# Dice-v1.net
KiCad netlist of a schematic drawn in EAGLE
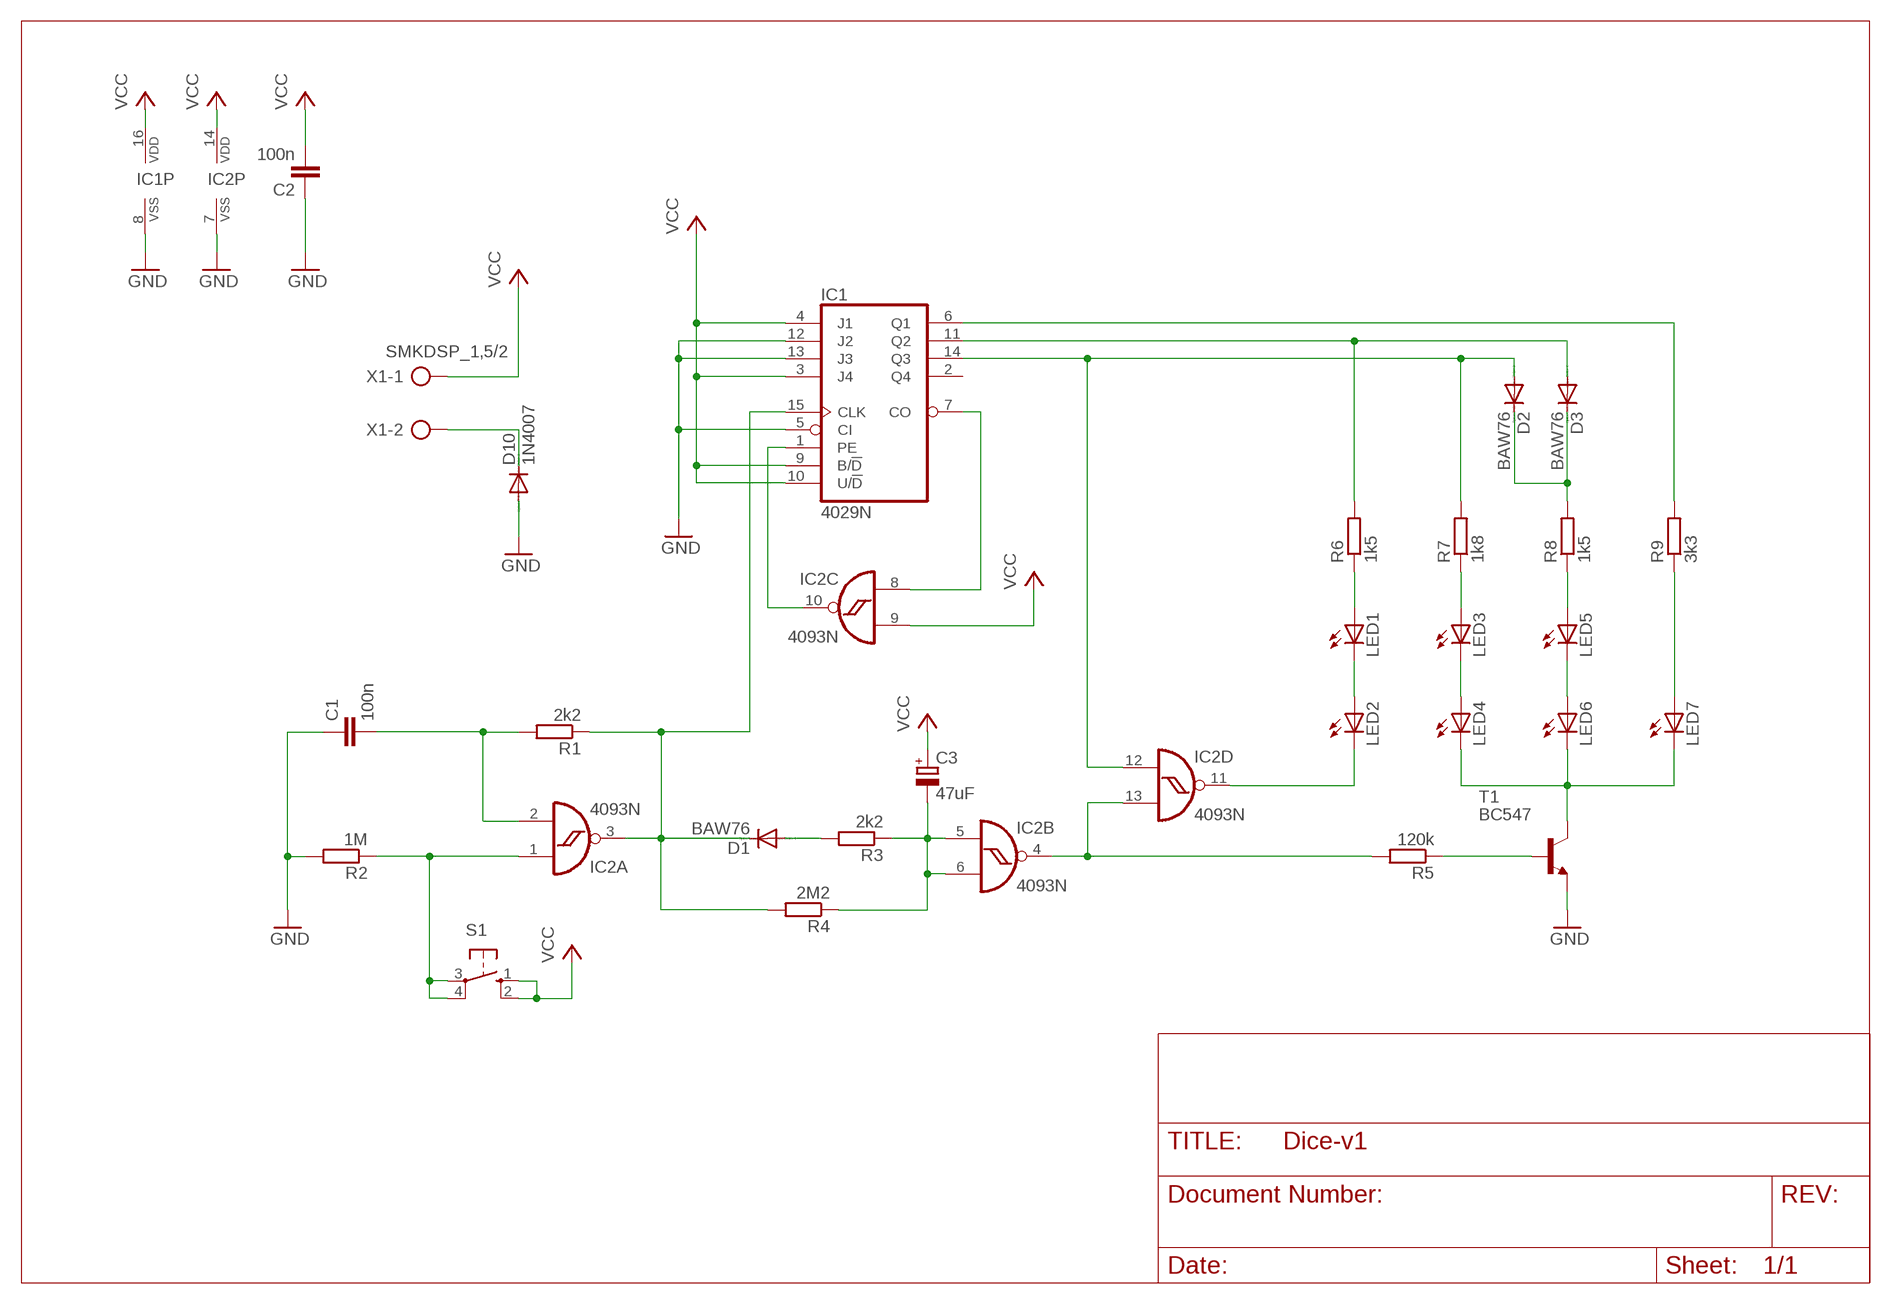
[diagram p0: schematic, sheet 1]

(export (version "E")
  (design (tool "Eeschema 10.0.6"))
  (components
    (comp (ref "C1")
      (value "100n")
      (footprint "eagle-import:C050-025X075")
      (libsource (lib "eagle-import") (part "C-EU050-025X075"))
    )
    (comp (ref "C2")
      (value "100n")
      (footprint "eagle-import:C050-025X075")
      (libsource (lib "eagle-import") (part "C-EU050-025X075"))
    )
    (comp (ref "C3")
      (value "47uF")
      (footprint "eagle-import:E2-5")
      (libsource (lib "eagle-import") (part "CPOL-EUE2-5"))
    )
    (comp (ref "D1")
      (value "BAW76")
      (footprint "eagle-import:DO35-10")
      (libsource (lib "eagle-import") (part "BAW75"))
    )
    (comp (ref "D2")
      (value "BAW76")
      (footprint "eagle-import:DO35-10")
      (libsource (lib "eagle-import") (part "BAW75"))
    )
    (comp (ref "D3")
      (value "BAW76")
      (footprint "eagle-import:DO35-10")
      (libsource (lib "eagle-import") (part "BAW75"))
    )
    (comp (ref "D10")
      (value "1N4007")
      (footprint "eagle-import:DO41-10")
      (libsource (lib "eagle-import") (part "1N4004"))
    )
    (comp (ref "IC1")
      (value "4029N")
      (footprint "eagle-import:DIL16")
      (libsource (lib "eagle-import") (part "4029N"))
    )
    (comp (ref "IC2")
      (value "4093N")
      (footprint "eagle-import:DIL14")
      (libsource (lib "eagle-import") (part "4093N"))
    )
    (comp (ref "LED1")
      (value "LED5MM")
      (footprint "eagle-import:LED5MM")
      (libsource (lib "eagle-import") (part "LED5MM"))
    )
    (comp (ref "LED2")
      (value "LED5MM")
      (footprint "eagle-import:LED5MM")
      (libsource (lib "eagle-import") (part "LED5MM"))
    )
    (comp (ref "LED3")
      (value "LED5MM")
      (footprint "eagle-import:LED5MM")
      (libsource (lib "eagle-import") (part "LED5MM"))
    )
    (comp (ref "LED4")
      (value "LED5MM")
      (footprint "eagle-import:LED5MM")
      (libsource (lib "eagle-import") (part "LED5MM"))
    )
    (comp (ref "LED5")
      (value "LED5MM")
      (footprint "eagle-import:LED5MM")
      (libsource (lib "eagle-import") (part "LED5MM"))
    )
    (comp (ref "LED6")
      (value "LED5MM")
      (footprint "eagle-import:LED5MM")
      (libsource (lib "eagle-import") (part "LED5MM"))
    )
    (comp (ref "LED7")
      (value "LED5MM")
      (footprint "eagle-import:LED5MM")
      (libsource (lib "eagle-import") (part "LED5MM"))
    )
    (comp (ref "R1")
      (value "2k2")
      (footprint "eagle-import:0207_10")
      (libsource (lib "eagle-import") (part "R-EU_0207/10"))
    )
    (comp (ref "R2")
      (value "1M")
      (footprint "eagle-import:0207_10")
      (libsource (lib "eagle-import") (part "R-EU_0207/10"))
    )
    (comp (ref "R3")
      (value "2k2")
      (footprint "eagle-import:0207_10")
      (libsource (lib "eagle-import") (part "R-EU_0207/10"))
    )
    (comp (ref "R4")
      (value "2M2")
      (footprint "eagle-import:0207_10")
      (libsource (lib "eagle-import") (part "R-EU_0207/10"))
    )
    (comp (ref "R5")
      (value "120k")
      (footprint "eagle-import:0207_10")
      (libsource (lib "eagle-import") (part "R-EU_0207/10"))
    )
    (comp (ref "R6")
      (value "1k5")
      (footprint "eagle-import:0207_10")
      (libsource (lib "eagle-import") (part "R-EU_0207/10"))
    )
    (comp (ref "R7")
      (value "1k8")
      (footprint "eagle-import:0207_10")
      (libsource (lib "eagle-import") (part "R-EU_0207/10"))
    )
    (comp (ref "R8")
      (value "1k5")
      (footprint "eagle-import:0207_10")
      (libsource (lib "eagle-import") (part "R-EU_0207/10"))
    )
    (comp (ref "R9")
      (value "3k3")
      (footprint "eagle-import:0207_10")
      (libsource (lib "eagle-import") (part "R-EU_0207/10"))
    )
    (comp (ref "S1")
      (value "10-XX")
      (footprint "eagle-import:B3F-10XX")
      (fields (field (name "MPN") "B3F-1000"))
      (libsource (lib "eagle-import") (part "10-XX"))
    )
    (comp (ref "T1")
      (value "BC547")
      (footprint "eagle-import:TO92")
      (libsource (lib "eagle-import") (part "BC547"))
    )
    (comp (ref "X1")
      (value "SMKDSP_1,5/2")
      (footprint "eagle-import:SMKDSP_1,5_2")
      (fields (field (name "MF") "FARNELL") (field (name "MPN") "1733570"))
      (libsource (lib "eagle-import") (part "SMKDSP_1,5/2"))
    )
  )
  (nets
    (net (code "1") (name "GND") (class "Default")
      (node (ref "C1") (pin "1") (pinfunction "1_1") (pintype "passive"))
      (node (ref "C2") (pin "1") (pinfunction "1_1") (pintype "passive"))
      (node (ref "D10") (pin "A") (pinfunction "A_A") (pintype "passive"))
      (node (ref "IC1") (pin "12") (pinfunction "J2_12") (pintype "input"))
      (node (ref "IC1") (pin "13") (pinfunction "J3_13") (pintype "input"))
      (node (ref "IC1") (pin "5") (pinfunction "CI_5") (pintype "input"))
      (node (ref "IC1") (pin "8") (pinfunction "VSS_8") (pintype "power_in"))
      (node (ref "IC2") (pin "7") (pinfunction "VSS_7") (pintype "power_in"))
      (node (ref "R2") (pin "2") (pinfunction "2_2") (pintype "passive"))
      (node (ref "T1") (pin "1") (pinfunction "E_1") (pintype "passive"))
    )
    (net (code "2") (name "Net-(D1-PadA)") (class "Default")
      (node (ref "D1") (pin "A") (pinfunction "A_A") (pintype "passive"))
      (node (ref "R3") (pin "2") (pinfunction "2_2") (pintype "passive"))
    )
    (net (code "3") (name "Net-(D2-PadC)") (class "Default")
      (node (ref "D2") (pin "C") (pinfunction "C_C") (pintype "passive"))
      (node (ref "D3") (pin "C") (pinfunction "C_C") (pintype "passive"))
      (node (ref "R8") (pin "2") (pinfunction "2_2") (pintype "passive"))
    )
    (net (code "4") (name "Net-(IC1A-CLK)") (class "Default")
      (node (ref "D1") (pin "C") (pinfunction "C_C") (pintype "passive"))
      (node (ref "IC1") (pin "15") (pinfunction "CLK_15") (pintype "input"))
      (node (ref "IC2") (pin "3") (pinfunction "O_3") (pintype "output"))
      (node (ref "R1") (pin "1") (pinfunction "1_1") (pintype "passive"))
      (node (ref "R4") (pin "2") (pinfunction "2_2") (pintype "passive"))
    )
    (net (code "5") (name "Net-(IC1A-CO)") (class "Default")
      (node (ref "IC1") (pin "7") (pinfunction "CO_7") (pintype "output"))
      (node (ref "IC2") (pin "8") (pinfunction "I0_8") (pintype "input"))
    )
    (net (code "6") (name "Net-(IC1A-PE)") (class "Default")
      (node (ref "IC1") (pin "1") (pinfunction "PE_1") (pintype "input"))
      (node (ref "IC2") (pin "10") (pinfunction "O_10") (pintype "output"))
    )
    (net (code "7") (name "Net-(IC1A-Q1)") (class "Default")
      (node (ref "IC1") (pin "6") (pinfunction "Q1_6") (pintype "output"))
      (node (ref "R9") (pin "2") (pinfunction "2_2") (pintype "passive"))
    )
    (net (code "8") (name "Net-(IC1A-Q2)") (class "Default")
      (node (ref "D3") (pin "A") (pinfunction "A_A") (pintype "passive"))
      (node (ref "IC1") (pin "11") (pinfunction "Q2_11") (pintype "output"))
      (node (ref "R6") (pin "2") (pinfunction "2_2") (pintype "passive"))
    )
    (net (code "9") (name "Net-(IC1A-Q3)") (class "Default")
      (node (ref "D2") (pin "A") (pinfunction "A_A") (pintype "passive"))
      (node (ref "IC1") (pin "14") (pinfunction "Q3_14") (pintype "output"))
      (node (ref "IC2") (pin "12") (pinfunction "I0_12") (pintype "input"))
      (node (ref "R7") (pin "2") (pinfunction "2_2") (pintype "passive"))
    )
    (net (code "10") (name "Net-(IC2A-I0)") (class "Default")
      (node (ref "IC2") (pin "1") (pinfunction "I0_1") (pintype "input"))
      (node (ref "R2") (pin "1") (pinfunction "1_1") (pintype "passive"))
      (node (ref "S1") (pin "3") (pinfunction "P_3") (pintype "passive"))
      (node (ref "S1") (pin "4") (pinfunction "P1_4") (pintype "passive"))
    )
    (net (code "11") (name "Net-(IC2A-I1)") (class "Default")
      (node (ref "C1") (pin "2") (pinfunction "2_2") (pintype "passive"))
      (node (ref "IC2") (pin "2") (pinfunction "I1_2") (pintype "input"))
      (node (ref "R1") (pin "2") (pinfunction "2_2") (pintype "passive"))
    )
    (net (code "12") (name "Net-(IC2B-I0)") (class "Default")
      (node (ref "C3") (pin "-") (pinfunction "-_-") (pintype "passive"))
      (node (ref "IC2") (pin "5") (pinfunction "I0_5") (pintype "input"))
      (node (ref "IC2") (pin "6") (pinfunction "I1_6") (pintype "input"))
      (node (ref "R3") (pin "1") (pinfunction "1_1") (pintype "passive"))
      (node (ref "R4") (pin "1") (pinfunction "1_1") (pintype "passive"))
    )
    (net (code "13") (name "Net-(IC2B-O)") (class "Default")
      (node (ref "IC2") (pin "13") (pinfunction "I1_13") (pintype "input"))
      (node (ref "IC2") (pin "4") (pinfunction "O_4") (pintype "output"))
      (node (ref "R5") (pin "2") (pinfunction "2_2") (pintype "passive"))
    )
    (net (code "14") (name "Net-(IC2D-O)") (class "Default")
      (node (ref "IC2") (pin "11") (pinfunction "O_11") (pintype "output"))
      (node (ref "LED2") (pin "K") (pinfunction "C_K") (pintype "passive"))
    )
    (net (code "15") (name "Net-(LED1-C)") (class "Default")
      (node (ref "LED1") (pin "K") (pinfunction "C_K") (pintype "passive"))
      (node (ref "LED2") (pin "A") (pinfunction "A_A") (pintype "passive"))
    )
    (net (code "16") (name "Net-(LED1-PadA)") (class "Default")
      (node (ref "LED1") (pin "A") (pinfunction "A_A") (pintype "passive"))
      (node (ref "R6") (pin "1") (pinfunction "1_1") (pintype "passive"))
    )
    (net (code "17") (name "Net-(LED3-C)") (class "Default")
      (node (ref "LED3") (pin "K") (pinfunction "C_K") (pintype "passive"))
      (node (ref "LED4") (pin "A") (pinfunction "A_A") (pintype "passive"))
    )
    (net (code "18") (name "Net-(LED3-PadA)") (class "Default")
      (node (ref "LED3") (pin "A") (pinfunction "A_A") (pintype "passive"))
      (node (ref "R7") (pin "1") (pinfunction "1_1") (pintype "passive"))
    )
    (net (code "19") (name "Net-(LED4-C)") (class "Default")
      (node (ref "LED4") (pin "K") (pinfunction "C_K") (pintype "passive"))
      (node (ref "LED6") (pin "K") (pinfunction "C_K") (pintype "passive"))
      (node (ref "LED7") (pin "K") (pinfunction "C_K") (pintype "passive"))
      (node (ref "T1") (pin "3") (pinfunction "C_3") (pintype "passive"))
    )
    (net (code "20") (name "Net-(LED5-C)") (class "Default")
      (node (ref "LED5") (pin "K") (pinfunction "C_K") (pintype "passive"))
      (node (ref "LED6") (pin "A") (pinfunction "A_A") (pintype "passive"))
    )
    (net (code "21") (name "Net-(LED5-PadA)") (class "Default")
      (node (ref "LED5") (pin "A") (pinfunction "A_A") (pintype "passive"))
      (node (ref "R8") (pin "1") (pinfunction "1_1") (pintype "passive"))
    )
    (net (code "22") (name "Net-(LED7-PadA)") (class "Default")
      (node (ref "LED7") (pin "A") (pinfunction "A_A") (pintype "passive"))
      (node (ref "R9") (pin "1") (pinfunction "1_1") (pintype "passive"))
    )
    (net (code "23") (name "Net-(T1-B)") (class "Default")
      (node (ref "R5") (pin "1") (pinfunction "1_1") (pintype "passive"))
      (node (ref "T1") (pin "2") (pinfunction "B_2") (pintype "passive"))
    )
    (net (code "24") (name "Net-(X1B-KL)") (class "Default")
      (node (ref "D10") (pin "C") (pinfunction "C_C") (pintype "passive"))
      (node (ref "X1") (pin "2") (pinfunction "KL_2") (pintype "passive"))
    )
    (net (code "25") (name "VCC") (class "Default")
      (node (ref "C2") (pin "2") (pinfunction "2_2") (pintype "passive"))
      (node (ref "C3") (pin "+") (pinfunction "+_+") (pintype "passive"))
      (node (ref "IC1") (pin "10") (pinfunction "U/~{D}_10") (pintype "input"))
      (node (ref "IC1") (pin "16") (pinfunction "VDD_16") (pintype "power_in"))
      (node (ref "IC1") (pin "3") (pinfunction "J4_3") (pintype "input"))
      (node (ref "IC1") (pin "4") (pinfunction "J1_4") (pintype "input"))
      (node (ref "IC1") (pin "9") (pinfunction "B/~{D}_9") (pintype "input"))
      (node (ref "IC2") (pin "14") (pinfunction "VDD_14") (pintype "power_in"))
      (node (ref "IC2") (pin "9") (pinfunction "I1_9") (pintype "input"))
      (node (ref "S1") (pin "1") (pinfunction "S_1") (pintype "passive"))
      (node (ref "S1") (pin "2") (pinfunction "S1_2") (pintype "passive"))
      (node (ref "X1") (pin "1") (pinfunction "KL_1") (pintype "passive"))
    )
    (net (code "26") (name "unconnected-(IC1A-Q4-Pad2)") (class "Default")
      (node (ref "IC1") (pin "2") (pinfunction "Q4_2") (pintype "output"))
    )
  )
)
